# step-drive.net
KiCad netlist of a schematic drawn in Altium Designer
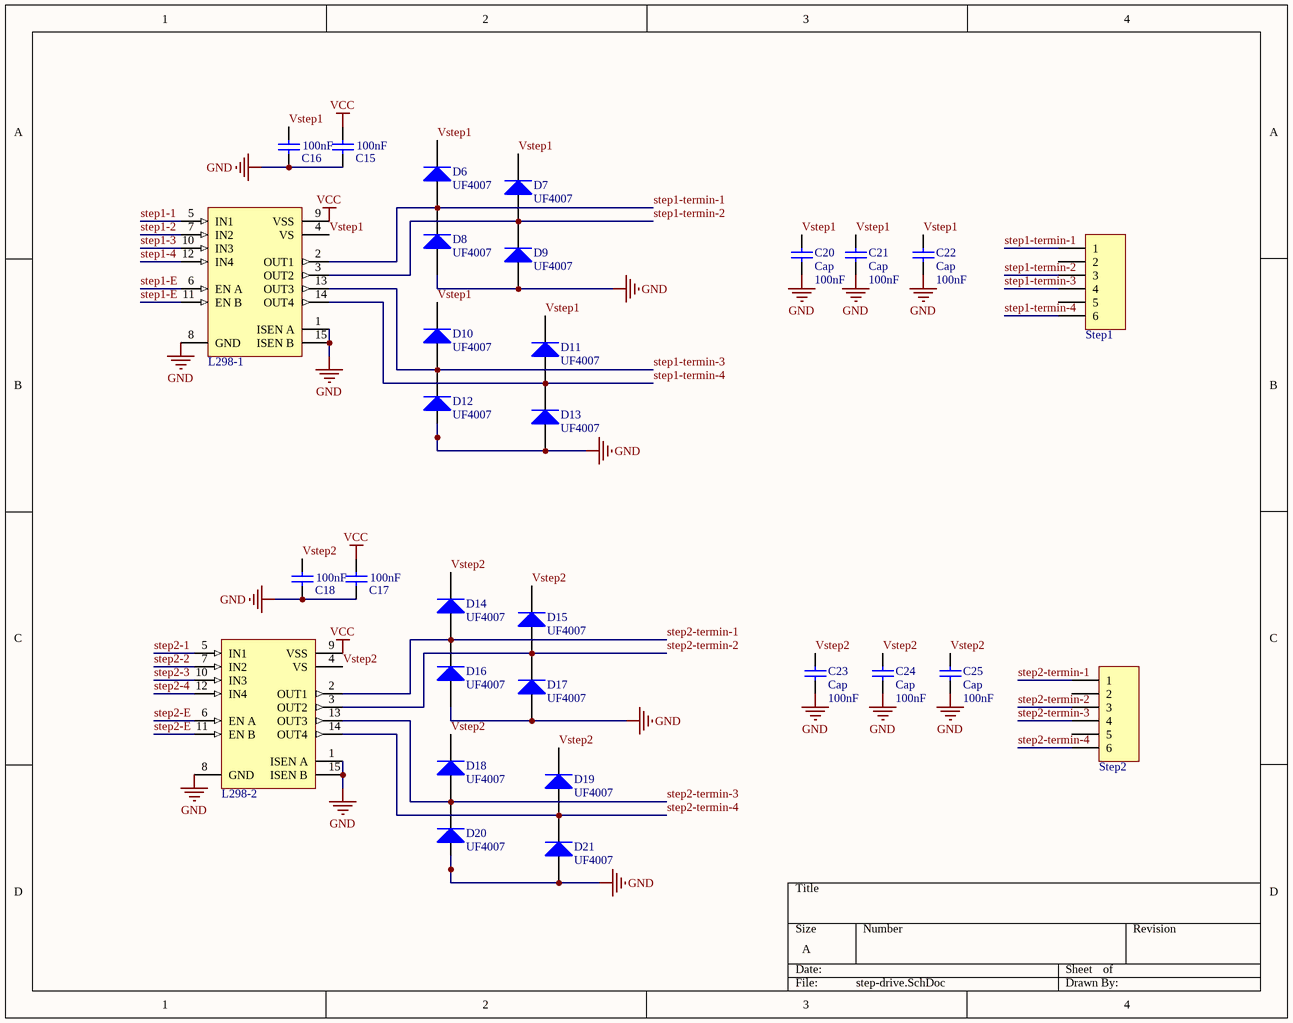
[diagram p0: step-drive.SchDoc]

(export (version "E")
  (design (tool "Eeschema 10.0.6"))
  (components
    (comp (ref "C15")
      (value "100nF")
      (footprint "CAP 1206/3216 - 0.8MM")
      (description "CAP-100Nf")
      (libsource (lib "Altium library (www.AVRelec.com)") (part "Cap ceramic"))
    )
    (comp (ref "C16")
      (value "100nF")
      (footprint "CAP 1206/3216 - 0.8MM")
      (description "CAP-100Nf")
      (libsource (lib "Altium library (www.AVRelec.com)") (part "Cap ceramic"))
    )
    (comp (ref "C17")
      (value "100nF")
      (footprint "CAP 1206/3216 - 0.8MM")
      (description "CAP-100Nf")
      (libsource (lib "Altium library (www.AVRelec.com)") (part "Cap ceramic"))
    )
    (comp (ref "C18")
      (value "100nF")
      (footprint "CAP 1206/3216 - 0.8MM")
      (description "CAP-100Nf")
      (libsource (lib "Altium library (www.AVRelec.com)") (part "Cap ceramic"))
    )
    (comp (ref "C20")
      (value "Cap")
      (footprint "CAP 1206/3216 - 0.8MM")
      (description "CAP-100Nf")
      (fields (field (name "ALTIUM_VALUE") "100nF"))
      (libsource (lib "Altium library (www.AVRelec.com)") (part "Cap ceramic"))
    )
    (comp (ref "C21")
      (value "Cap")
      (footprint "CAP 1206/3216 - 0.8MM")
      (description "CAP-100Nf")
      (fields (field (name "ALTIUM_VALUE") "100nF"))
      (libsource (lib "Altium library (www.AVRelec.com)") (part "Cap ceramic"))
    )
    (comp (ref "C22")
      (value "Cap")
      (footprint "CAP 1206/3216 - 0.8MM")
      (description "CAP-100Nf")
      (fields (field (name "ALTIUM_VALUE") "100nF"))
      (libsource (lib "Altium library (www.AVRelec.com)") (part "Cap ceramic"))
    )
    (comp (ref "C23")
      (value "Cap")
      (footprint "CAP 1206/3216 - 0.8MM")
      (description "CAP-100Nf")
      (fields (field (name "ALTIUM_VALUE") "100nF"))
      (libsource (lib "Altium library (www.AVRelec.com)") (part "Cap ceramic"))
    )
    (comp (ref "C24")
      (value "Cap")
      (footprint "CAP 1206/3216 - 0.8MM")
      (description "CAP-100Nf")
      (fields (field (name "ALTIUM_VALUE") "100nF"))
      (libsource (lib "Altium library (www.AVRelec.com)") (part "Cap ceramic"))
    )
    (comp (ref "C25")
      (value "Cap")
      (footprint "CAP 1206/3216 - 0.8MM")
      (description "CAP-100Nf")
      (fields (field (name "ALTIUM_VALUE") "100nF"))
      (libsource (lib "Altium library (www.AVRelec.com)") (part "Cap ceramic"))
    )
    (comp (ref "D6")
      (value "UF4007")
      (footprint "DO214AC SMA")
      (description "1 Amp General Purpose Rectifier")
      (fields (field (name "PUBLISHER") "Altium Limited"))
      (libsource (lib "Miscellaneous Devices") (part "Diode 1N4007"))
    )
    (comp (ref "D7")
      (value "UF4007")
      (footprint "DO214AC SMA")
      (description "1 Amp General Purpose Rectifier")
      (fields (field (name "PUBLISHER") "Altium Limited"))
      (libsource (lib "Miscellaneous Devices") (part "Diode 1N4007"))
    )
    (comp (ref "D8")
      (value "UF4007")
      (footprint "DO214AC SMA")
      (description "1 Amp General Purpose Rectifier")
      (fields (field (name "PUBLISHER") "Altium Limited"))
      (libsource (lib "Miscellaneous Devices") (part "Diode 1N4007"))
    )
    (comp (ref "D9")
      (value "UF4007")
      (footprint "DO214AC SMA")
      (description "1 Amp General Purpose Rectifier")
      (fields (field (name "PUBLISHER") "Altium Limited"))
      (libsource (lib "Miscellaneous Devices") (part "Diode 1N4007"))
    )
    (comp (ref "D10")
      (value "UF4007")
      (footprint "DO214AC SMA")
      (description "1 Amp General Purpose Rectifier")
      (fields (field (name "PUBLISHER") "Altium Limited"))
      (libsource (lib "Miscellaneous Devices") (part "Diode 1N4007"))
    )
    (comp (ref "D11")
      (value "UF4007")
      (footprint "DO214AC SMA")
      (description "1 Amp General Purpose Rectifier")
      (fields (field (name "PUBLISHER") "Altium Limited"))
      (libsource (lib "Miscellaneous Devices") (part "Diode 1N4007"))
    )
    (comp (ref "D12")
      (value "UF4007")
      (footprint "DO214AC SMA")
      (description "1 Amp General Purpose Rectifier")
      (fields (field (name "PUBLISHER") "Altium Limited"))
      (libsource (lib "Miscellaneous Devices") (part "Diode 1N4007"))
    )
    (comp (ref "D13")
      (value "UF4007")
      (footprint "DO214AC SMA")
      (description "1 Amp General Purpose Rectifier")
      (fields (field (name "PUBLISHER") "Altium Limited"))
      (libsource (lib "Miscellaneous Devices") (part "Diode 1N4007"))
    )
    (comp (ref "D14")
      (value "UF4007")
      (footprint "DO214AC SMA")
      (description "1 Amp General Purpose Rectifier")
      (fields (field (name "PUBLISHER") "Altium Limited"))
      (libsource (lib "Miscellaneous Devices") (part "Diode 1N4007"))
    )
    (comp (ref "D15")
      (value "UF4007")
      (footprint "DO214AC SMA")
      (description "1 Amp General Purpose Rectifier")
      (fields (field (name "PUBLISHER") "Altium Limited"))
      (libsource (lib "Miscellaneous Devices") (part "Diode 1N4007"))
    )
    (comp (ref "D16")
      (value "UF4007")
      (footprint "DO214AC SMA")
      (description "1 Amp General Purpose Rectifier")
      (fields (field (name "PUBLISHER") "Altium Limited"))
      (libsource (lib "Miscellaneous Devices") (part "Diode 1N4007"))
    )
    (comp (ref "D17")
      (value "UF4007")
      (footprint "DO214AC SMA")
      (description "1 Amp General Purpose Rectifier")
      (fields (field (name "PUBLISHER") "Altium Limited"))
      (libsource (lib "Miscellaneous Devices") (part "Diode 1N4007"))
    )
    (comp (ref "D18")
      (value "UF4007")
      (footprint "DO214AC SMA")
      (description "1 Amp General Purpose Rectifier")
      (fields (field (name "PUBLISHER") "Altium Limited"))
      (libsource (lib "Miscellaneous Devices") (part "Diode 1N4007"))
    )
    (comp (ref "D19")
      (value "UF4007")
      (footprint "DO214AC SMA")
      (description "1 Amp General Purpose Rectifier")
      (fields (field (name "PUBLISHER") "Altium Limited"))
      (libsource (lib "Miscellaneous Devices") (part "Diode 1N4007"))
    )
    (comp (ref "D20")
      (value "UF4007")
      (footprint "DO214AC SMA")
      (description "1 Amp General Purpose Rectifier")
      (fields (field (name "PUBLISHER") "Altium Limited"))
      (libsource (lib "Miscellaneous Devices") (part "Diode 1N4007"))
    )
    (comp (ref "D21")
      (value "UF4007")
      (footprint "DO214AC SMA")
      (description "1 Amp General Purpose Rectifier")
      (fields (field (name "PUBLISHER") "Altium Limited"))
      (libsource (lib "Miscellaneous Devices") (part "Diode 1N4007"))
    )
    (comp (ref "L298-1") (value "L298") (footprint "L298") (libsource (lib "Mine-IC") (part "L298")))
    (comp (ref "L298-2") (value "L298") (footprint "L298") (libsource (lib "Mine-IC") (part "L298")))
    (comp (ref "Step1") (value "H-1x6") (footprint "H-1x6") (libsource (lib "Mine-Discreet") (part "H-1x6")))
    (comp (ref "Step2") (value "H-1x6") (footprint "H-1x6") (libsource (lib "Mine-Discreet") (part "H-1x6")))
  )
  (nets
    (net (code "1") (name "/Vstep1") (class "Default")
      (node (ref "C16") (pin "2") (pinfunction "2_2") (pintype "passive"))
      (node (ref "C20") (pin "1") (pinfunction "1_1") (pintype "passive"))
      (node (ref "C21") (pin "1") (pinfunction "1_1") (pintype "passive"))
      (node (ref "C22") (pin "1") (pinfunction "1_1") (pintype "passive"))
      (node (ref "D10") (pin "2") (pinfunction "K_2") (pintype "passive"))
      (node (ref "D11") (pin "2") (pinfunction "K_2") (pintype "passive"))
      (node (ref "D6") (pin "2") (pinfunction "K_2") (pintype "passive"))
      (node (ref "D7") (pin "2") (pinfunction "K_2") (pintype "passive"))
      (node (ref "L298-1") (pin "4") (pinfunction "VS_4") (pintype "power_in"))
    )
    (net (code "2") (name "/Vstep2") (class "Default")
      (node (ref "C18") (pin "2") (pinfunction "2_2") (pintype "passive"))
      (node (ref "C23") (pin "1") (pinfunction "1_1") (pintype "passive"))
      (node (ref "C24") (pin "1") (pinfunction "1_1") (pintype "passive"))
      (node (ref "C25") (pin "1") (pinfunction "1_1") (pintype "passive"))
      (node (ref "D14") (pin "2") (pinfunction "K_2") (pintype "passive"))
      (node (ref "D15") (pin "2") (pinfunction "K_2") (pintype "passive"))
      (node (ref "D18") (pin "2") (pinfunction "K_2") (pintype "passive"))
      (node (ref "D19") (pin "2") (pinfunction "K_2") (pintype "passive"))
      (node (ref "L298-2") (pin "4") (pinfunction "VS_4") (pintype "power_in"))
    )
    (net (code "3") (name "/step1-1") (class "Default")
      (node (ref "L298-1") (pin "5") (pinfunction "IN1_5") (pintype "input"))
    )
    (net (code "4") (name "/step1-2") (class "Default")
      (node (ref "L298-1") (pin "7") (pinfunction "IN2_7") (pintype "input"))
    )
    (net (code "5") (name "/step1-3") (class "Default")
      (node (ref "L298-1") (pin "10") (pinfunction "IN3_10") (pintype "input"))
    )
    (net (code "6") (name "/step1-4") (class "Default")
      (node (ref "L298-1") (pin "12") (pinfunction "IN4_12") (pintype "input"))
    )
    (net (code "7") (name "/step1-E") (class "Default")
      (node (ref "L298-1") (pin "11") (pinfunction "EN_B_11") (pintype "input"))
      (node (ref "L298-1") (pin "6") (pinfunction "EN_A_6") (pintype "input"))
    )
    (net (code "8") (name "/step1-termin-1") (class "Default")
      (node (ref "D6") (pin "1") (pinfunction "A_1") (pintype "passive"))
      (node (ref "D8") (pin "2") (pinfunction "K_2") (pintype "passive"))
      (node (ref "L298-1") (pin "2") (pinfunction "OUT1_2") (pintype "output"))
      (node (ref "Step1") (pin "1") (pinfunction "1_1") (pintype "passive"))
    )
    (net (code "9") (name "/step1-termin-2") (class "Default")
      (node (ref "D7") (pin "1") (pinfunction "A_1") (pintype "passive"))
      (node (ref "D9") (pin "2") (pinfunction "K_2") (pintype "passive"))
      (node (ref "L298-1") (pin "3") (pinfunction "OUT2_3") (pintype "output"))
      (node (ref "Step1") (pin "3") (pinfunction "3_3") (pintype "passive"))
    )
    (net (code "10") (name "/step1-termin-3") (class "Default")
      (node (ref "D10") (pin "1") (pinfunction "A_1") (pintype "passive"))
      (node (ref "D12") (pin "2") (pinfunction "K_2") (pintype "passive"))
      (node (ref "L298-1") (pin "13") (pinfunction "OUT3_13") (pintype "output"))
      (node (ref "Step1") (pin "4") (pinfunction "4_4") (pintype "passive"))
    )
    (net (code "11") (name "/step1-termin-4") (class "Default")
      (node (ref "D11") (pin "1") (pinfunction "A_1") (pintype "passive"))
      (node (ref "D13") (pin "2") (pinfunction "K_2") (pintype "passive"))
      (node (ref "L298-1") (pin "14") (pinfunction "OUT4_14") (pintype "output"))
      (node (ref "Step1") (pin "6") (pinfunction "6_6") (pintype "passive"))
    )
    (net (code "12") (name "/step2-1") (class "Default")
      (node (ref "L298-2") (pin "5") (pinfunction "IN1_5") (pintype "input"))
    )
    (net (code "13") (name "/step2-2") (class "Default")
      (node (ref "L298-2") (pin "7") (pinfunction "IN2_7") (pintype "input"))
    )
    (net (code "14") (name "/step2-3") (class "Default")
      (node (ref "L298-2") (pin "10") (pinfunction "IN3_10") (pintype "input"))
    )
    (net (code "15") (name "/step2-4") (class "Default")
      (node (ref "L298-2") (pin "12") (pinfunction "IN4_12") (pintype "input"))
    )
    (net (code "16") (name "/step2-E") (class "Default")
      (node (ref "L298-2") (pin "11") (pinfunction "EN_B_11") (pintype "input"))
      (node (ref "L298-2") (pin "6") (pinfunction "EN_A_6") (pintype "input"))
    )
    (net (code "17") (name "/step2-termin-1") (class "Default")
      (node (ref "D14") (pin "1") (pinfunction "A_1") (pintype "passive"))
      (node (ref "D16") (pin "2") (pinfunction "K_2") (pintype "passive"))
      (node (ref "L298-2") (pin "2") (pinfunction "OUT1_2") (pintype "output"))
      (node (ref "Step2") (pin "1") (pinfunction "1_1") (pintype "passive"))
    )
    (net (code "18") (name "/step2-termin-2") (class "Default")
      (node (ref "D15") (pin "1") (pinfunction "A_1") (pintype "passive"))
      (node (ref "D17") (pin "2") (pinfunction "K_2") (pintype "passive"))
      (node (ref "L298-2") (pin "3") (pinfunction "OUT2_3") (pintype "output"))
      (node (ref "Step2") (pin "3") (pinfunction "3_3") (pintype "passive"))
    )
    (net (code "19") (name "/step2-termin-3") (class "Default")
      (node (ref "D18") (pin "1") (pinfunction "A_1") (pintype "passive"))
      (node (ref "D20") (pin "2") (pinfunction "K_2") (pintype "passive"))
      (node (ref "L298-2") (pin "13") (pinfunction "OUT3_13") (pintype "output"))
      (node (ref "Step2") (pin "4") (pinfunction "4_4") (pintype "passive"))
    )
    (net (code "20") (name "/step2-termin-4") (class "Default")
      (node (ref "D19") (pin "1") (pinfunction "A_1") (pintype "passive"))
      (node (ref "D21") (pin "2") (pinfunction "K_2") (pintype "passive"))
      (node (ref "L298-2") (pin "14") (pinfunction "OUT4_14") (pintype "output"))
      (node (ref "Step2") (pin "6") (pinfunction "6_6") (pintype "passive"))
    )
    (net (code "21") (name "GND") (class "Default")
      (node (ref "C15") (pin "1") (pinfunction "1_1") (pintype "passive"))
      (node (ref "C16") (pin "1") (pinfunction "1_1") (pintype "passive"))
      (node (ref "C17") (pin "1") (pinfunction "1_1") (pintype "passive"))
      (node (ref "C18") (pin "1") (pinfunction "1_1") (pintype "passive"))
      (node (ref "C20") (pin "2") (pinfunction "2_2") (pintype "passive"))
      (node (ref "C21") (pin "2") (pinfunction "2_2") (pintype "passive"))
      (node (ref "C22") (pin "2") (pinfunction "2_2") (pintype "passive"))
      (node (ref "C23") (pin "2") (pinfunction "2_2") (pintype "passive"))
      (node (ref "C24") (pin "2") (pinfunction "2_2") (pintype "passive"))
      (node (ref "C25") (pin "2") (pinfunction "2_2") (pintype "passive"))
      (node (ref "D12") (pin "1") (pinfunction "A_1") (pintype "passive"))
      (node (ref "D13") (pin "1") (pinfunction "A_1") (pintype "passive"))
      (node (ref "D16") (pin "1") (pinfunction "A_1") (pintype "passive"))
      (node (ref "D17") (pin "1") (pinfunction "A_1") (pintype "passive"))
      (node (ref "D20") (pin "1") (pinfunction "A_1") (pintype "passive"))
      (node (ref "D21") (pin "1") (pinfunction "A_1") (pintype "passive"))
      (node (ref "D8") (pin "1") (pinfunction "A_1") (pintype "passive"))
      (node (ref "D9") (pin "1") (pinfunction "A_1") (pintype "passive"))
      (node (ref "L298-1") (pin "1") (pinfunction "ISEN_A_1") (pintype "passive"))
      (node (ref "L298-1") (pin "15") (pinfunction "ISEN_B_15") (pintype "passive"))
      (node (ref "L298-1") (pin "8") (pinfunction "GND_8") (pintype "power_in"))
      (node (ref "L298-2") (pin "1") (pinfunction "ISEN_A_1") (pintype "passive"))
      (node (ref "L298-2") (pin "15") (pinfunction "ISEN_B_15") (pintype "passive"))
      (node (ref "L298-2") (pin "8") (pinfunction "GND_8") (pintype "power_in"))
    )
    (net (code "22") (name "VCC") (class "Default")
      (node (ref "C15") (pin "2") (pinfunction "2_2") (pintype "passive"))
      (node (ref "C17") (pin "2") (pinfunction "2_2") (pintype "passive"))
      (node (ref "L298-1") (pin "9") (pinfunction "VSS_9") (pintype "power_in"))
      (node (ref "L298-2") (pin "9") (pinfunction "VSS_9") (pintype "power_in"))
    )
    (net (code "23") (name "unconnected-(Step1-Pad2)") (class "Default")
      (node (ref "Step1") (pin "2") (pinfunction "2_2") (pintype "passive"))
    )
    (net (code "24") (name "unconnected-(Step1-Pad5)") (class "Default")
      (node (ref "Step1") (pin "5") (pinfunction "5_5") (pintype "passive"))
    )
    (net (code "25") (name "unconnected-(Step2-Pad2)") (class "Default")
      (node (ref "Step2") (pin "2") (pinfunction "2_2") (pintype "passive"))
    )
    (net (code "26") (name "unconnected-(Step2-Pad5)") (class "Default")
      (node (ref "Step2") (pin "5") (pinfunction "5_5") (pintype "passive"))
    )
  )
)
